# farmBot_schematic_v22.net
KiCad netlist of a schematic drawn in EAGLE
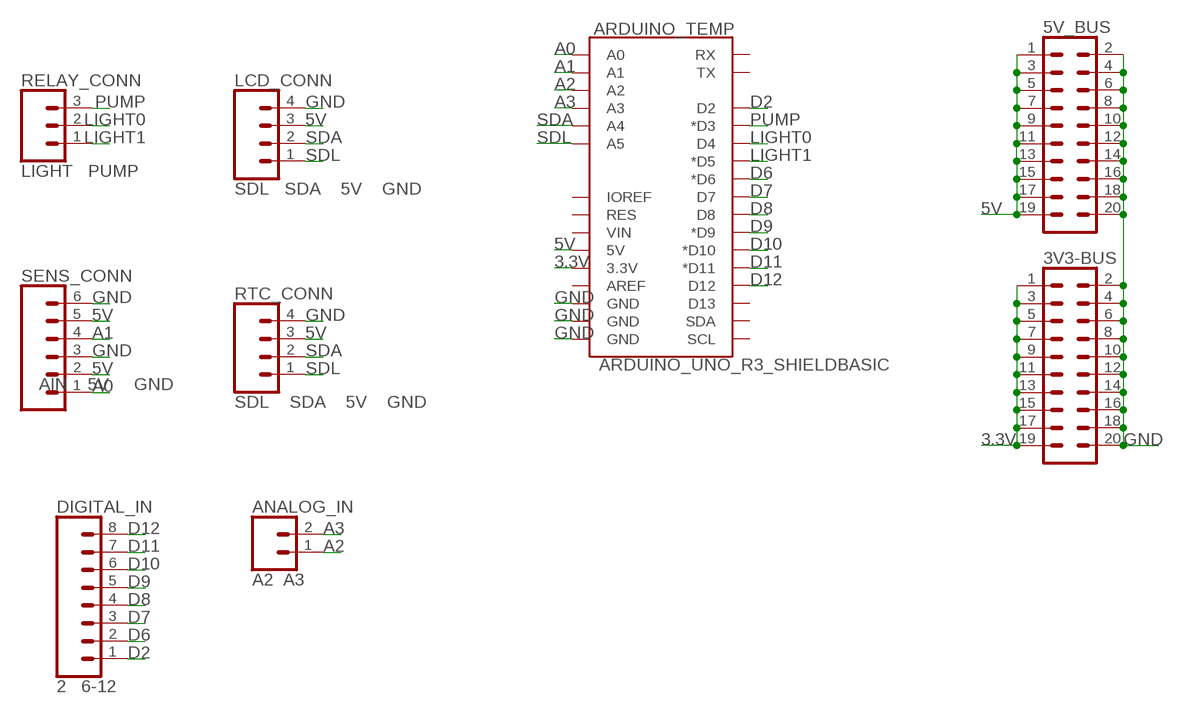
[diagram p0: schematic, sheet 1]

(export (version "E")
  (design (tool "Eeschema 10.0.6"))
  (components
    (comp (ref "3V3-BUS")
      (value "CONN_10X2")
      (footprint "eagle-import:2X10")
      (libsource (lib "eagle-import") (part "CONN_10X2"))
    )
    (comp (ref "5V_BUS")
      (value "CONN_10X2")
      (footprint "eagle-import:2X10")
      (libsource (lib "eagle-import") (part "CONN_10X2"))
    )
    (comp (ref "ANALOG_IN")
      (value "A2 A3")
      (footprint "eagle-import:1X02")
      (libsource (lib "eagle-import") (part "CONN_02"))
    )
    (comp (ref "ARDUINO_TEMP")
      (value "ARDUINO_UNO_R3_SHIELDBASIC")
      (footprint "eagle-import:UNO_R3_SHIELD")
      (libsource (lib "eagle-import") (part "ARDUINO_UNO_R3_SHIELDBASIC"))
    )
    (comp (ref "DIGITAL_IN")
      (value "2 6-12")
      (footprint "eagle-import:1X08")
      (libsource (lib "eagle-import") (part "CONN_08{dblquote}"))
    )
    (comp (ref "LCD_CONN")
      (value "SDL SDA 5V GND")
      (footprint "eagle-import:1X04")
      (libsource (lib "eagle-import") (part "CONN_04"))
    )
    (comp (ref "RELAY_CONN")
      (value "LIGHT PUMP")
      (footprint "eagle-import:1X03")
      (libsource (lib "eagle-import") (part "CONN_03"))
    )
    (comp (ref "RTC_CONN")
      (value "SDL SDA 5V GND")
      (footprint "eagle-import:1X04")
      (libsource (lib "eagle-import") (part "CONN_04"))
    )
    (comp (ref "SENS_CONN")
      (value "AIN 5V GND")
      (footprint "eagle-import:1X06")
      (libsource (lib "eagle-import") (part "CONN_06SILK_FEMALE_PTH"))
    )
  )
  (nets
    (net (code "1") (name "/3.3V") (class "Default")
      (node (ref "3V3-BUS") (pin "1") (pinfunction "1_1") (pintype "passive"))
      (node (ref "3V3-BUS") (pin "11") (pinfunction "11_11") (pintype "passive"))
      (node (ref "3V3-BUS") (pin "13") (pinfunction "13_13") (pintype "passive"))
      (node (ref "3V3-BUS") (pin "15") (pinfunction "15_15") (pintype "passive"))
      (node (ref "3V3-BUS") (pin "17") (pinfunction "17_17") (pintype "passive"))
      (node (ref "3V3-BUS") (pin "19") (pinfunction "19_19") (pintype "passive"))
      (node (ref "3V3-BUS") (pin "3") (pinfunction "3_3") (pintype "passive"))
      (node (ref "3V3-BUS") (pin "5") (pinfunction "5_5") (pintype "passive"))
      (node (ref "3V3-BUS") (pin "7") (pinfunction "7_7") (pintype "passive"))
      (node (ref "3V3-BUS") (pin "9") (pinfunction "9_9") (pintype "passive"))
      (node (ref "ARDUINO_TEMP") (pin "3.3V") (pinfunction "3.3V_3.3V") (pintype "bidirectional"))
    )
    (net (code "2") (name "/5V") (class "Default")
      (node (ref "5V_BUS") (pin "1") (pinfunction "1_1") (pintype "passive"))
      (node (ref "5V_BUS") (pin "11") (pinfunction "11_11") (pintype "passive"))
      (node (ref "5V_BUS") (pin "13") (pinfunction "13_13") (pintype "passive"))
      (node (ref "5V_BUS") (pin "15") (pinfunction "15_15") (pintype "passive"))
      (node (ref "5V_BUS") (pin "17") (pinfunction "17_17") (pintype "passive"))
      (node (ref "5V_BUS") (pin "19") (pinfunction "19_19") (pintype "passive"))
      (node (ref "5V_BUS") (pin "3") (pinfunction "3_3") (pintype "passive"))
      (node (ref "5V_BUS") (pin "5") (pinfunction "5_5") (pintype "passive"))
      (node (ref "5V_BUS") (pin "7") (pinfunction "7_7") (pintype "passive"))
      (node (ref "5V_BUS") (pin "9") (pinfunction "9_9") (pintype "passive"))
      (node (ref "ARDUINO_TEMP") (pin "5V") (pinfunction "5V_5V") (pintype "bidirectional"))
      (node (ref "LCD_CONN") (pin "3") (pinfunction "3_3") (pintype "passive"))
      (node (ref "RTC_CONN") (pin "3") (pinfunction "3_3") (pintype "passive"))
      (node (ref "SENS_CONN") (pin "2") (pinfunction "2_2") (pintype "passive"))
      (node (ref "SENS_CONN") (pin "5") (pinfunction "5_5") (pintype "passive"))
    )
    (net (code "3") (name "/A0") (class "Default")
      (node (ref "ARDUINO_TEMP") (pin "A0") (pinfunction "A0_A0") (pintype "bidirectional"))
      (node (ref "SENS_CONN") (pin "1") (pinfunction "1_1") (pintype "passive"))
    )
    (net (code "4") (name "/A1") (class "Default")
      (node (ref "ARDUINO_TEMP") (pin "A1") (pinfunction "A1_A1") (pintype "bidirectional"))
      (node (ref "SENS_CONN") (pin "4") (pinfunction "4_4") (pintype "passive"))
    )
    (net (code "5") (name "/A2") (class "Default")
      (node (ref "ANALOG_IN") (pin "1") (pinfunction "1_1") (pintype "passive"))
      (node (ref "ARDUINO_TEMP") (pin "A2") (pinfunction "A2_A2") (pintype "bidirectional"))
    )
    (net (code "6") (name "/A3") (class "Default")
      (node (ref "ANALOG_IN") (pin "2") (pinfunction "2_2") (pintype "passive"))
      (node (ref "ARDUINO_TEMP") (pin "A3") (pinfunction "A3_A3") (pintype "bidirectional"))
    )
    (net (code "7") (name "/D2") (class "Default")
      (node (ref "ARDUINO_TEMP") (pin "D2") (pinfunction "D2_D2") (pintype "bidirectional"))
      (node (ref "DIGITAL_IN") (pin "1") (pinfunction "1_1") (pintype "passive"))
    )
    (net (code "8") (name "/D6") (class "Default")
      (node (ref "ARDUINO_TEMP") (pin "D6") (pinfunction "*D6_D6") (pintype "bidirectional"))
      (node (ref "DIGITAL_IN") (pin "2") (pinfunction "2_2") (pintype "passive"))
    )
    (net (code "9") (name "/D7") (class "Default")
      (node (ref "ARDUINO_TEMP") (pin "D7") (pinfunction "D7_D7") (pintype "bidirectional"))
      (node (ref "DIGITAL_IN") (pin "3") (pinfunction "3_3") (pintype "passive"))
    )
    (net (code "10") (name "/D8") (class "Default")
      (node (ref "ARDUINO_TEMP") (pin "D8") (pinfunction "D8_D8") (pintype "bidirectional"))
      (node (ref "DIGITAL_IN") (pin "4") (pinfunction "4_4") (pintype "passive"))
    )
    (net (code "11") (name "/D9") (class "Default")
      (node (ref "ARDUINO_TEMP") (pin "D9") (pinfunction "*D9_D9") (pintype "bidirectional"))
      (node (ref "DIGITAL_IN") (pin "5") (pinfunction "5_5") (pintype "passive"))
    )
    (net (code "12") (name "/D10") (class "Default")
      (node (ref "ARDUINO_TEMP") (pin "D10") (pinfunction "*D10_D10") (pintype "bidirectional"))
      (node (ref "DIGITAL_IN") (pin "6") (pinfunction "6_6") (pintype "passive"))
    )
    (net (code "13") (name "/D11") (class "Default")
      (node (ref "ARDUINO_TEMP") (pin "D11") (pinfunction "*D11_D11") (pintype "bidirectional"))
      (node (ref "DIGITAL_IN") (pin "7") (pinfunction "7_7") (pintype "passive"))
    )
    (net (code "14") (name "/D12") (class "Default")
      (node (ref "ARDUINO_TEMP") (pin "D12") (pinfunction "D12_D12") (pintype "bidirectional"))
      (node (ref "DIGITAL_IN") (pin "8") (pinfunction "8_8") (pintype "passive"))
    )
    (net (code "15") (name "/GND") (class "Default")
      (node (ref "3V3-BUS") (pin "10") (pinfunction "10_10") (pintype "passive"))
      (node (ref "3V3-BUS") (pin "12") (pinfunction "12_12") (pintype "passive"))
      (node (ref "3V3-BUS") (pin "14") (pinfunction "14_14") (pintype "passive"))
      (node (ref "3V3-BUS") (pin "16") (pinfunction "16_16") (pintype "passive"))
      (node (ref "3V3-BUS") (pin "18") (pinfunction "18_18") (pintype "passive"))
      (node (ref "3V3-BUS") (pin "2") (pinfunction "2_2") (pintype "passive"))
      (node (ref "3V3-BUS") (pin "20") (pinfunction "20_20") (pintype "passive"))
      (node (ref "3V3-BUS") (pin "4") (pinfunction "4_4") (pintype "passive"))
      (node (ref "3V3-BUS") (pin "6") (pinfunction "6_6") (pintype "passive"))
      (node (ref "3V3-BUS") (pin "8") (pinfunction "8_8") (pintype "passive"))
      (node (ref "5V_BUS") (pin "10") (pinfunction "10_10") (pintype "passive"))
      (node (ref "5V_BUS") (pin "12") (pinfunction "12_12") (pintype "passive"))
      (node (ref "5V_BUS") (pin "14") (pinfunction "14_14") (pintype "passive"))
      (node (ref "5V_BUS") (pin "16") (pinfunction "16_16") (pintype "passive"))
      (node (ref "5V_BUS") (pin "18") (pinfunction "18_18") (pintype "passive"))
      (node (ref "5V_BUS") (pin "2") (pinfunction "2_2") (pintype "passive"))
      (node (ref "5V_BUS") (pin "20") (pinfunction "20_20") (pintype "passive"))
      (node (ref "5V_BUS") (pin "4") (pinfunction "4_4") (pintype "passive"))
      (node (ref "5V_BUS") (pin "6") (pinfunction "6_6") (pintype "passive"))
      (node (ref "5V_BUS") (pin "8") (pinfunction "8_8") (pintype "passive"))
      (node (ref "ARDUINO_TEMP") (pin "GND@0") (pinfunction "GND_GND@0") (pintype "bidirectional"))
      (node (ref "ARDUINO_TEMP") (pin "GND@1") (pinfunction "GND_GND@1") (pintype "bidirectional"))
      (node (ref "ARDUINO_TEMP") (pin "GND@2") (pinfunction "GND_GND@2") (pintype "bidirectional"))
      (node (ref "LCD_CONN") (pin "4") (pinfunction "4_4") (pintype "passive"))
      (node (ref "RTC_CONN") (pin "4") (pinfunction "4_4") (pintype "passive"))
      (node (ref "SENS_CONN") (pin "3") (pinfunction "3_3") (pintype "passive"))
      (node (ref "SENS_CONN") (pin "6") (pinfunction "6_6") (pintype "passive"))
    )
    (net (code "16") (name "/LIGHT0") (class "Default")
      (node (ref "ARDUINO_TEMP") (pin "D4") (pinfunction "D4_D4") (pintype "bidirectional"))
      (node (ref "RELAY_CONN") (pin "2") (pinfunction "2_2") (pintype "passive"))
    )
    (net (code "17") (name "/LIGHT1") (class "Default")
      (node (ref "ARDUINO_TEMP") (pin "D5") (pinfunction "*D5_D5") (pintype "bidirectional"))
      (node (ref "RELAY_CONN") (pin "1") (pinfunction "1_1") (pintype "passive"))
    )
    (net (code "18") (name "/PUMP") (class "Default")
      (node (ref "ARDUINO_TEMP") (pin "D3") (pinfunction "*D3_D3") (pintype "bidirectional"))
      (node (ref "RELAY_CONN") (pin "3") (pinfunction "3_3") (pintype "passive"))
    )
    (net (code "19") (name "/SDA") (class "Default")
      (node (ref "ARDUINO_TEMP") (pin "A4") (pinfunction "A4_A4") (pintype "bidirectional"))
      (node (ref "LCD_CONN") (pin "2") (pinfunction "2_2") (pintype "passive"))
      (node (ref "RTC_CONN") (pin "2") (pinfunction "2_2") (pintype "passive"))
    )
    (net (code "20") (name "/SDL") (class "Default")
      (node (ref "ARDUINO_TEMP") (pin "A5") (pinfunction "A5_A5") (pintype "bidirectional"))
      (node (ref "LCD_CONN") (pin "1") (pinfunction "1_1") (pintype "passive"))
      (node (ref "RTC_CONN") (pin "1") (pinfunction "1_1") (pintype "passive"))
    )
    (net (code "21") (name "unconnected-(ARDUINO_TEMP-PadAREF)") (class "Default")
      (node (ref "ARDUINO_TEMP") (pin "AREF") (pinfunction "AREF_AREF") (pintype "bidirectional"))
    )
    (net (code "22") (name "unconnected-(ARDUINO_TEMP-PadD13)") (class "Default")
      (node (ref "ARDUINO_TEMP") (pin "D13") (pinfunction "D13_D13") (pintype "bidirectional"))
    )
    (net (code "23") (name "unconnected-(ARDUINO_TEMP-PadIOREF)") (class "Default")
      (node (ref "ARDUINO_TEMP") (pin "IOREF") (pinfunction "IOREF_IOREF") (pintype "bidirectional"))
    )
    (net (code "24") (name "unconnected-(ARDUINO_TEMP-PadRES)") (class "Default")
      (node (ref "ARDUINO_TEMP") (pin "RES") (pinfunction "RES_RES") (pintype "bidirectional"))
    )
    (net (code "25") (name "unconnected-(ARDUINO_TEMP-PadRX)") (class "Default")
      (node (ref "ARDUINO_TEMP") (pin "RX") (pinfunction "RX_RX") (pintype "bidirectional"))
    )
    (net (code "26") (name "unconnected-(ARDUINO_TEMP-PadSCL)") (class "Default")
      (node (ref "ARDUINO_TEMP") (pin "SCL") (pinfunction "SCL_SCL") (pintype "bidirectional"))
    )
    (net (code "27") (name "unconnected-(ARDUINO_TEMP-PadSDA)") (class "Default")
      (node (ref "ARDUINO_TEMP") (pin "SDA") (pinfunction "SDA_SDA") (pintype "bidirectional"))
    )
    (net (code "28") (name "unconnected-(ARDUINO_TEMP-PadTX)") (class "Default")
      (node (ref "ARDUINO_TEMP") (pin "TX") (pinfunction "TX_TX") (pintype "bidirectional"))
    )
    (net (code "29") (name "unconnected-(ARDUINO_TEMP-PadVIN)") (class "Default")
      (node (ref "ARDUINO_TEMP") (pin "VIN") (pinfunction "VIN_VIN") (pintype "bidirectional"))
    )
  )
)
